# 03_MCU_STM32.net
KiCad netlist of a schematic drawn in Altium Designer
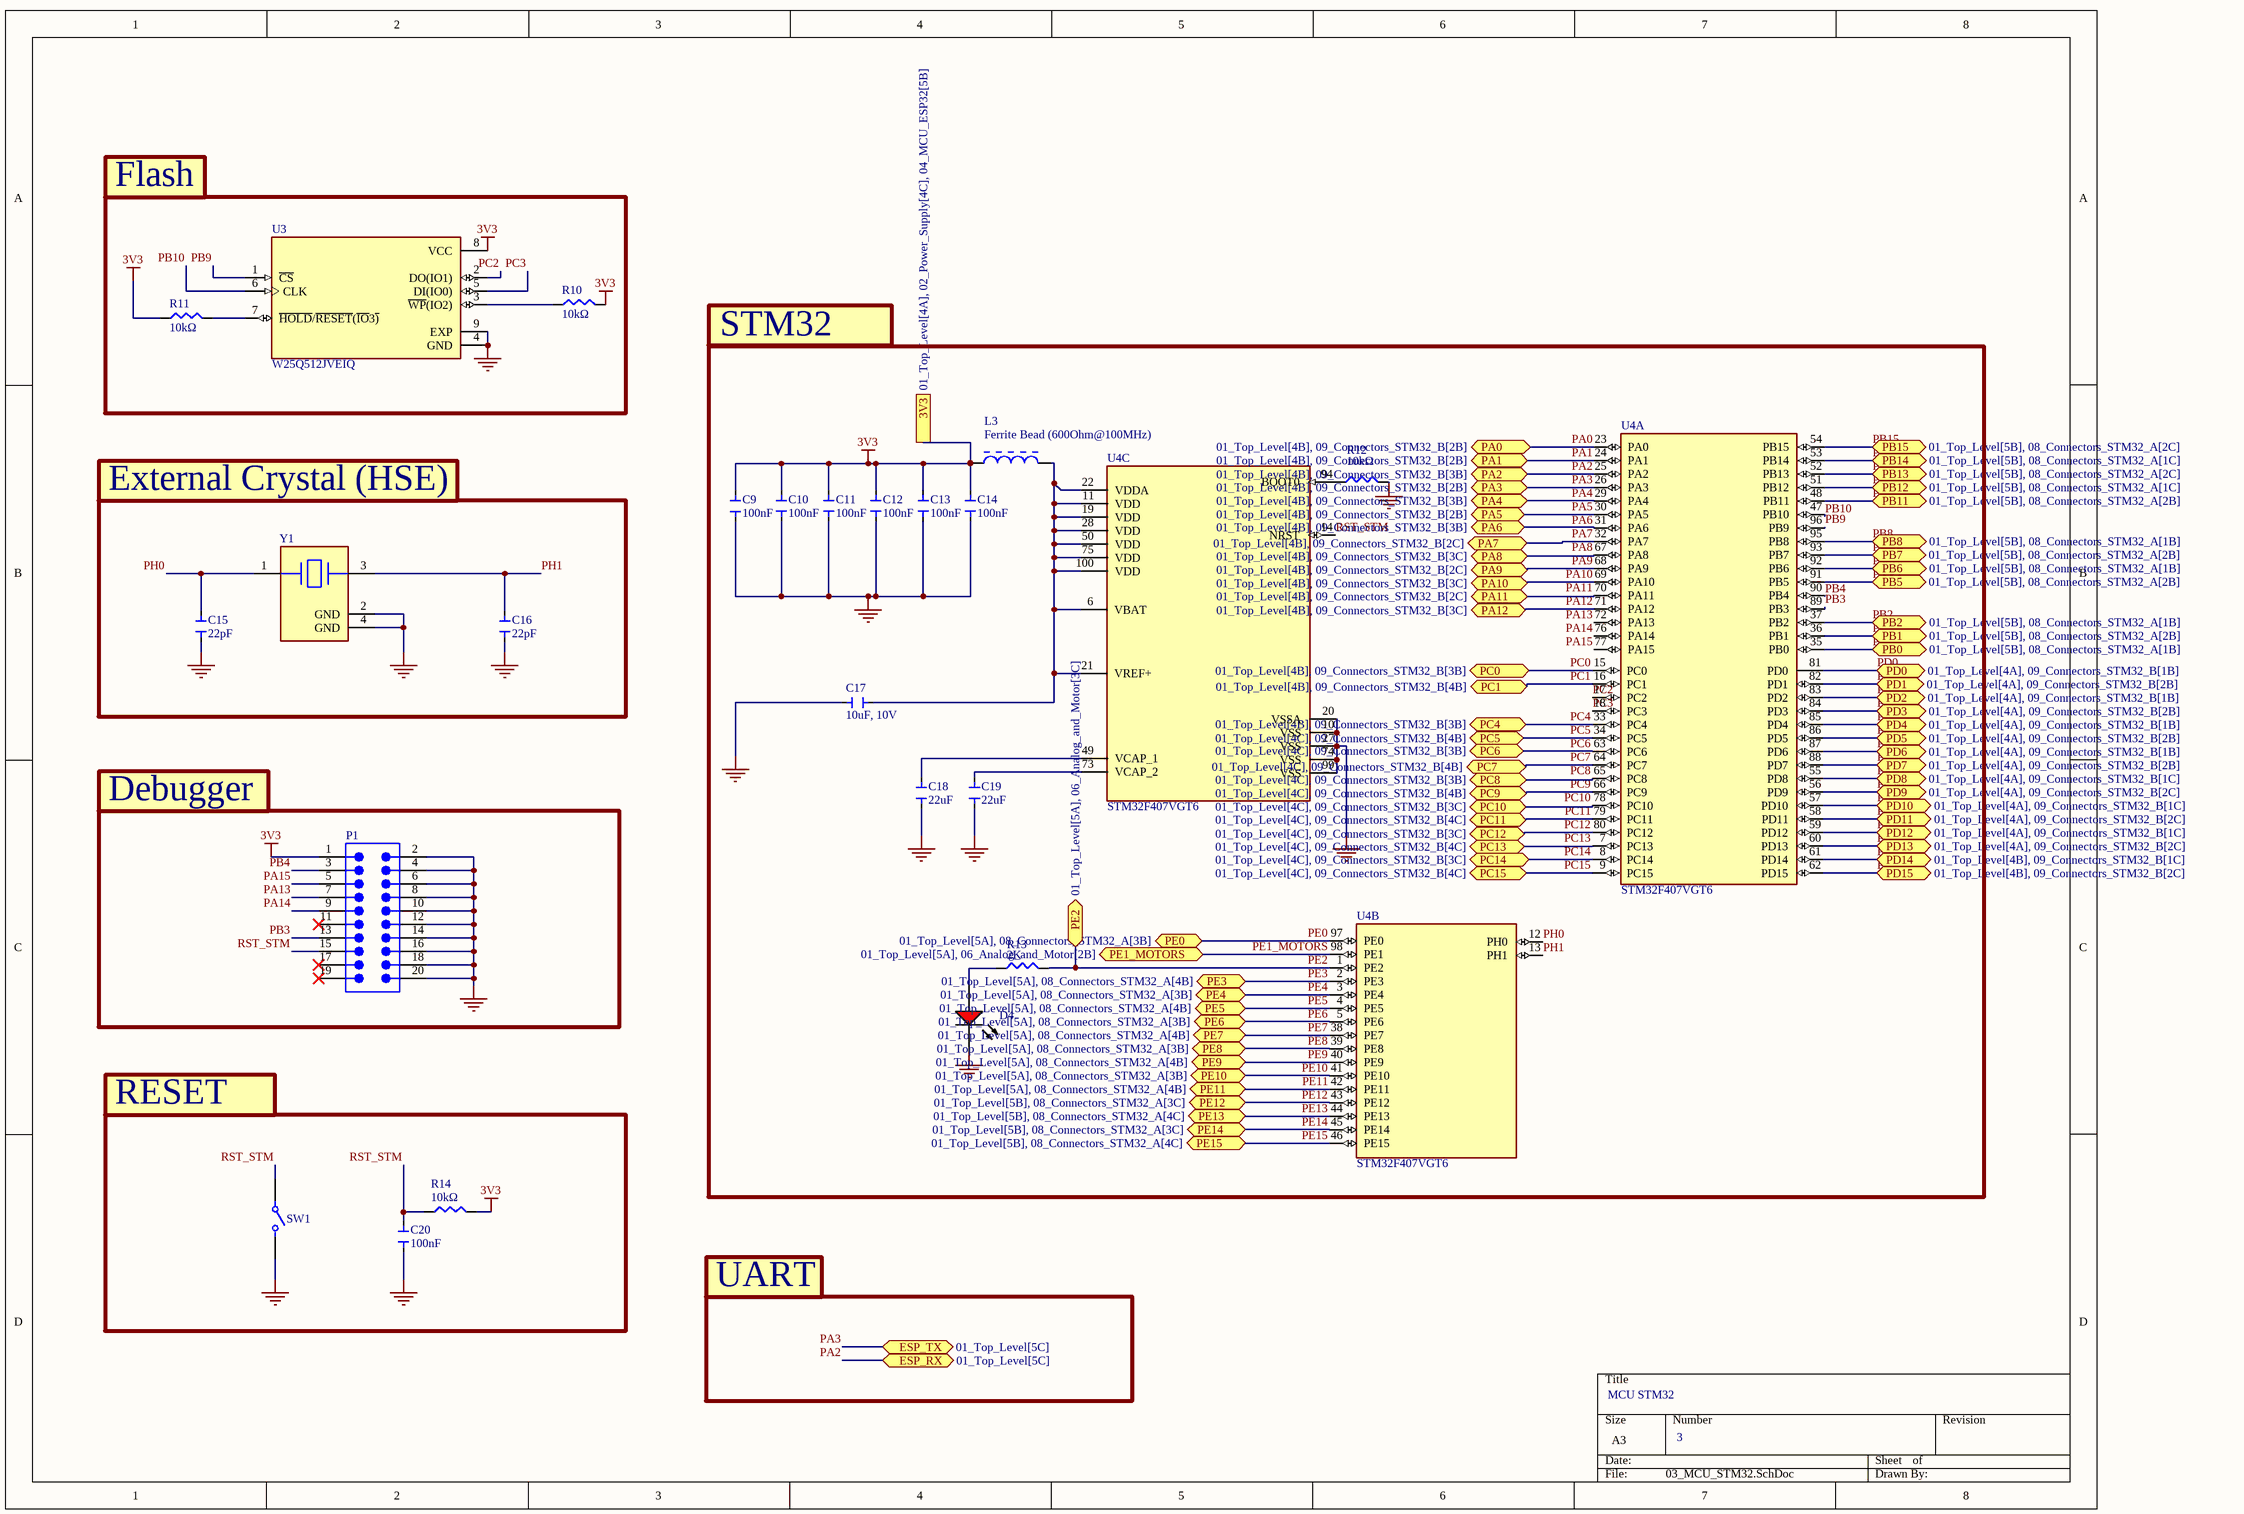
[diagram p0: 03_MCU_STM32.SchDoc]

(export (version "E")
  (design (tool "Eeschema 10.0.6"))
  (components
    (comp (ref "C9")
      (value "100nF")
      (footprint "CAP_100nF")
      (description "CAP 100nF 50V X7R ±10% 0603 Ceramic Capacitors RoHS")
      (fields
        (field (name "MANUFACTURER") "YAGEO")
        (field (name "MANUFACTURER PART NUMBER") "CC0603KRX7R9BB104")
      )
      (libsource (lib "Components_Schlib") (part "CAP_100nF"))
    )
    (comp (ref "C10")
      (value "100nF")
      (footprint "CAP_100nF")
      (description "CAP 100nF 50V X7R ±10% 0603 Ceramic Capacitors RoHS")
      (fields
        (field (name "MANUFACTURER") "YAGEO")
        (field (name "MANUFACTURER PART NUMBER") "CC0603KRX7R9BB104")
      )
      (libsource (lib "Components_Schlib") (part "CAP_100nF"))
    )
    (comp (ref "C11")
      (value "100nF")
      (footprint "CAP_100nF")
      (description "CAP 100nF 50V X7R ±10% 0603 Ceramic Capacitors RoHS")
      (fields
        (field (name "MANUFACTURER") "YAGEO")
        (field (name "MANUFACTURER PART NUMBER") "CC0603KRX7R9BB104")
      )
      (libsource (lib "Components_Schlib") (part "CAP_100nF"))
    )
    (comp (ref "C12")
      (value "100nF")
      (footprint "CAP_100nF")
      (description "CAP 100nF 50V X7R ±10% 0603 Ceramic Capacitors RoHS")
      (fields
        (field (name "MANUFACTURER") "YAGEO")
        (field (name "MANUFACTURER PART NUMBER") "CC0603KRX7R9BB104")
      )
      (libsource (lib "Components_Schlib") (part "CAP_100nF"))
    )
    (comp (ref "C13")
      (value "100nF")
      (footprint "CAP_100nF")
      (description "CAP 100nF 50V X7R ±10% 0603 Ceramic Capacitors RoHS")
      (fields
        (field (name "MANUFACTURER") "YAGEO")
        (field (name "MANUFACTURER PART NUMBER") "CC0603KRX7R9BB104")
      )
      (libsource (lib "Components_Schlib") (part "CAP_100nF"))
    )
    (comp (ref "C14")
      (value "100nF")
      (footprint "CAP_100nF")
      (description "CAP 100nF 50V X7R ±10% 0603 Ceramic Capacitors RoHS")
      (fields
        (field (name "MANUFACTURER") "YAGEO")
        (field (name "MANUFACTURER PART NUMBER") "CC0603KRX7R9BB104")
      )
      (libsource (lib "Components_Schlib") (part "CAP_100nF"))
    )
    (comp (ref "C15")
      (value "22pF")
      (footprint "CAP_22uF")
      (description "CAP 22uF 25V X5R ±20% 0805 Ceramic Capacitors RoHS")
      (fields
        (field (name "MANUFACTURER") "Samsung Electro-Mechanics")
        (field (name "MANUFACTURER PART NUMBER") "CL21A226MAYNNNE")
      )
      (libsource (lib "Components_Schlib") (part "CAP_22uF"))
    )
    (comp (ref "C16")
      (value "22pF")
      (footprint "CAP_22uF")
      (description "CAP 22uF 25V X5R ±20% 0805 Ceramic Capacitors RoHS")
      (fields
        (field (name "MANUFACTURER") "Samsung Electro-Mechanics")
        (field (name "MANUFACTURER PART NUMBER") "CL21A226MAYNNNE")
      )
      (libsource (lib "Components_Schlib") (part "CAP_22uF"))
    )
    (comp (ref "C17")
      (value "10uF, 10V")
      (footprint "CAP_10uF")
      (description "CAP CER 10UF 10V X5R 0402")
      (fields
        (field (name "MANUFACTURER") "Samsung Electro-Mechanics")
        (field (name "MANUFACTURER PART NUMBER") "C307415")
      )
      (libsource (lib "Components_Schlib") (part "CAP_0402_10UF"))
    )
    (comp (ref "C18")
      (value "22uF")
      (footprint "CAP_22uF")
      (description "CAP 22uF 25V X5R ±20% 0805 Ceramic Capacitors RoHS")
      (fields
        (field (name "MANUFACTURER") "Samsung Electro-Mechanics")
        (field (name "MANUFACTURER PART NUMBER") "CL21A226MAYNNNE")
      )
      (libsource (lib "Components_Schlib") (part "CAP_22uF"))
    )
    (comp (ref "C19")
      (value "22uF")
      (footprint "CAP_22uF")
      (description "CAP 22uF 25V X5R ±20% 0805 Ceramic Capacitors RoHS")
      (fields
        (field (name "MANUFACTURER") "Samsung Electro-Mechanics")
        (field (name "MANUFACTURER PART NUMBER") "CL21A226MAYNNNE")
      )
      (libsource (lib "Components_Schlib") (part "CAP_22uF"))
    )
    (comp (ref "C20")
      (value "100nF")
      (footprint "CAP_100nF")
      (description "CAP 100nF 50V X7R ±10% 0603 Ceramic Capacitors RoHS")
      (fields
        (field (name "MANUFACTURER") "YAGEO")
        (field (name "MANUFACTURER PART NUMBER") "CC0603KRX7R9BB104")
      )
      (libsource (lib "Components_Schlib") (part "CAP_100nF"))
    )
    (comp (ref "D4")
      (value "304090041")
      (footprint "LED-2P-2.28-3MM_A")
      (description "Red LED, 80 mW, 30 mA, -25 to 85 degC, 2-Pin THD")
      (fields (field (name "MANUFACTURER") "Shenzhen CGX"))
      (libsource (lib "Youssef Adel") (part "LED-RED-AK-2"))
    )
    (comp (ref "L3")
      (value "BLM18AG121SN1D")
      (footprint "MURA-BLM18-F-H1-CHIP-2_V")
      (fields (field (name "TOLERANCE") "25%") (field (name "MANUFACTURER") "Murata"))
      (libsource (lib "Youssef Adel") (part "IND-FB-2"))
    )
    (comp (ref "P1")
      (value "61002021121")
      (footprint "61002021121")
      (description "SMT Vertical Pin Header WR-PHD, Pitch 2.54 mm, Dual Row, 20 pins")
      (libsource (lib "Altium Content Vault") (part "Header_Male_2R_20P"))
    )
    (comp (ref "R10")
      (value "10kΩ")
      (footprint "RES_10K")
      (description "100mW Thin Film Resistor ±0.1% ±10ppm/℃ 10kΩ 0603 Chip Resistor - Surface Mount ROHS")
      (fields
        (field (name "MANUFACTURER") "Yageo Group")
        (field (name "MANUFACTURER PART NUMBER") "RT0603BRB07169KL")
      )
      (libsource (lib "Components_Schlib") (part "RES_0603_10K"))
    )
    (comp (ref "R11")
      (value "10kΩ")
      (footprint "RES_10K")
      (description "100mW Thin Film Resistor ±0.1% ±10ppm/℃ 10kΩ 0603 Chip Resistor - Surface Mount ROHS")
      (fields
        (field (name "MANUFACTURER") "Yageo Group")
        (field (name "MANUFACTURER PART NUMBER") "RT0603BRB07169KL")
      )
      (libsource (lib "Components_Schlib") (part "RES_0603_10K"))
    )
    (comp (ref "R12")
      (value "10kΩ")
      (footprint "RES_10K")
      (description "100mW Thin Film Resistor ±0.1% ±10ppm/℃ 10kΩ 0603 Chip Resistor - Surface Mount ROHS")
      (fields
        (field (name "MANUFACTURER") "Yageo Group")
        (field (name "MANUFACTURER PART NUMBER") "RT0603BRB07169KL")
      )
      (libsource (lib "Components_Schlib") (part "RES_0603_10K"))
    )
    (comp (ref "R13")
      (value "2K")
      (footprint "RES_2K")
      (description "100mW 2KΩ 75V Thick Film Resistor ±100ppm/℃ ±1% 0603 Chip Resistor - Surface Mount RoHS")
      (libsource (lib "Components_Schlib") (part "RSE_0603_2K"))
    )
    (comp (ref "R14")
      (value "10kΩ")
      (footprint "RES_10K")
      (description "100mW Thin Film Resistor ±0.1% ±10ppm/℃ 10kΩ 0603 Chip Resistor - Surface Mount ROHS")
      (fields
        (field (name "MANUFACTURER") "Yageo Group")
        (field (name "MANUFACTURER PART NUMBER") "RT0603BRB07169KL")
      )
      (libsource (lib "Components_Schlib") (part "RES_0603_10K"))
    )
    (comp (ref "SW1")
      (value "EVP-BD6C1A000")
      (footprint "FP-EVP-BD6C1A000-MFG")
      (description "EVP-BD6C1A000 Switch Tactile N.O. SPST Round Button J-Bend 0.05A 12VDC 3.5N SMD Automotive T/R")
      (libsource (lib "Altium Content Vault") (part "2b0b2b19372efd94fa7681498149756"))
    )
    (comp (ref "U3")
      (value "W25Q512JVEIQ")
      (footprint "SON127P600X800X80-9N")
      (description "FLASH - NOR Memory IC 512Mb (64M x 8) SPI - Quad I/O 133 MHz 8-WSON (8x6)")
      (fields (field (name "MF") "Winbond Electronics"))
      (libsource (lib "Components_Schlib") (part "W25Q512JVEIQ"))
    )
    (comp (ref "U4")
      (value "STM32F407VGT6")
      (footprint "QFP50P1600X1600X160-100N")
      (fields (field (name "MF") "STMicroelectronics"))
      (libsource (lib "Components_Schlib") (part "STM32F407VGT6"))
    )
    (comp (ref "Y1")
      (value "ABM11AIG-32.000MHZ-4-T3")
      (footprint "FP-ABM11AIG-MFG")
      (description "Crystal 32MHz ±30ppm 10pF SMD-4 2.5mm x 2mm Automotive")
      (libsource (lib "Altium Content Vault") (part "51b5329859b7ce12e0c2ce5858bdf70"))
    )
  )
  (nets
    (net (code "1") (name "/PA0") (class "Default")
      (node (ref "U4") (pin "23") (pinfunction "PA0_23") (pintype "bidirectional"))
    )
    (net (code "2") (name "/PA1") (class "Default")
      (node (ref "U4") (pin "24") (pinfunction "PA1_24") (pintype "bidirectional"))
    )
    (net (code "3") (name "/PA2") (class "Default")
      (node (ref "U4") (pin "25") (pinfunction "PA2_25") (pintype "bidirectional"))
    )
    (net (code "4") (name "/PA3") (class "Default")
      (node (ref "U4") (pin "26") (pinfunction "PA3_26") (pintype "bidirectional"))
    )
    (net (code "5") (name "/PA4") (class "Default")
      (node (ref "U4") (pin "29") (pinfunction "PA4_29") (pintype "bidirectional"))
    )
    (net (code "6") (name "/PA5") (class "Default")
      (node (ref "U4") (pin "30") (pinfunction "PA5_30") (pintype "bidirectional"))
    )
    (net (code "7") (name "/PA6") (class "Default")
      (node (ref "U4") (pin "31") (pinfunction "PA6_31") (pintype "bidirectional"))
    )
    (net (code "8") (name "/PA7") (class "Default")
      (node (ref "U4") (pin "32") (pinfunction "PA7_32") (pintype "bidirectional"))
    )
    (net (code "9") (name "/PA8") (class "Default")
      (node (ref "U4") (pin "67") (pinfunction "PA8_67") (pintype "bidirectional"))
    )
    (net (code "10") (name "/PA9") (class "Default")
      (node (ref "U4") (pin "68") (pinfunction "PA9_68") (pintype "bidirectional"))
    )
    (net (code "11") (name "/PA10") (class "Default")
      (node (ref "U4") (pin "69") (pinfunction "PA10_69") (pintype "bidirectional"))
    )
    (net (code "12") (name "/PA11") (class "Default")
      (node (ref "U4") (pin "70") (pinfunction "PA11_70") (pintype "bidirectional"))
    )
    (net (code "13") (name "/PA12") (class "Default")
      (node (ref "U4") (pin "71") (pinfunction "PA12_71") (pintype "bidirectional"))
    )
    (net (code "14") (name "/PA13") (class "Default")
      (node (ref "P1") (pin "7") (pinfunction "7_7") (pintype "passive"))
      (node (ref "U4") (pin "72") (pinfunction "PA13_72") (pintype "bidirectional"))
    )
    (net (code "15") (name "/PA14") (class "Default")
      (node (ref "P1") (pin "9") (pinfunction "9_9") (pintype "passive"))
      (node (ref "U4") (pin "76") (pinfunction "PA14_76") (pintype "bidirectional"))
    )
    (net (code "16") (name "/PA15") (class "Default")
      (node (ref "P1") (pin "5") (pinfunction "5_5") (pintype "passive"))
      (node (ref "U4") (pin "77") (pinfunction "PA15_77") (pintype "bidirectional"))
    )
    (net (code "17") (name "/PB0") (class "Default")
      (node (ref "U4") (pin "35") (pinfunction "PB0_35") (pintype "bidirectional"))
    )
    (net (code "18") (name "/PB1") (class "Default")
      (node (ref "U4") (pin "36") (pinfunction "PB1_36") (pintype "bidirectional"))
    )
    (net (code "19") (name "/PB2") (class "Default")
      (node (ref "U4") (pin "37") (pinfunction "PB2_37") (pintype "bidirectional"))
    )
    (net (code "20") (name "/PB3") (class "Default")
      (node (ref "P1") (pin "13") (pinfunction "13_13") (pintype "passive"))
      (node (ref "U4") (pin "89") (pinfunction "PB3_89") (pintype "bidirectional"))
    )
    (net (code "21") (name "/PB4") (class "Default")
      (node (ref "P1") (pin "3") (pinfunction "3_3") (pintype "passive"))
      (node (ref "U4") (pin "90") (pinfunction "PB4_90") (pintype "bidirectional"))
    )
    (net (code "22") (name "/PB5") (class "Default")
      (node (ref "U4") (pin "91") (pinfunction "PB5_91") (pintype "bidirectional"))
    )
    (net (code "23") (name "/PB6") (class "Default")
      (node (ref "U4") (pin "92") (pinfunction "PB6_92") (pintype "bidirectional"))
    )
    (net (code "24") (name "/PB7") (class "Default")
      (node (ref "U4") (pin "93") (pinfunction "PB7_93") (pintype "bidirectional"))
    )
    (net (code "25") (name "/PB8") (class "Default")
      (node (ref "U4") (pin "95") (pinfunction "PB8_95") (pintype "bidirectional"))
    )
    (net (code "26") (name "/PB9") (class "Default")
      (node (ref "U3") (pin "1") (pinfunction "~{CS}_1") (pintype "input"))
      (node (ref "U4") (pin "96") (pinfunction "PB9_96") (pintype "bidirectional"))
    )
    (net (code "27") (name "/PB10") (class "Default")
      (node (ref "U3") (pin "6") (pinfunction "CLK_6") (pintype "input"))
      (node (ref "U4") (pin "47") (pinfunction "PB10_47") (pintype "bidirectional"))
    )
    (net (code "28") (name "/PB11") (class "Default")
      (node (ref "U4") (pin "48") (pinfunction "PB11_48") (pintype "bidirectional"))
    )
    (net (code "29") (name "/PB12") (class "Default")
      (node (ref "U4") (pin "51") (pinfunction "PB12_51") (pintype "bidirectional"))
    )
    (net (code "30") (name "/PB13") (class "Default")
      (node (ref "U4") (pin "52") (pinfunction "PB13_52") (pintype "bidirectional"))
    )
    (net (code "31") (name "/PB14") (class "Default")
      (node (ref "U4") (pin "53") (pinfunction "PB14_53") (pintype "bidirectional"))
    )
    (net (code "32") (name "/PB15") (class "Default")
      (node (ref "U4") (pin "54") (pinfunction "PB15_54") (pintype "bidirectional"))
    )
    (net (code "33") (name "/PC0") (class "Default")
      (node (ref "U4") (pin "15") (pinfunction "PC0_15") (pintype "bidirectional"))
    )
    (net (code "34") (name "/PC1") (class "Default")
      (node (ref "U4") (pin "16") (pinfunction "PC1_16") (pintype "bidirectional"))
    )
    (net (code "35") (name "/PC2") (class "Default")
      (node (ref "U3") (pin "2") (pinfunction "DO(IO1)_2") (pintype "bidirectional"))
      (node (ref "U4") (pin "17") (pinfunction "PC2_17") (pintype "bidirectional"))
    )
    (net (code "36") (name "/PC3") (class "Default")
      (node (ref "U3") (pin "5") (pinfunction "DI(IO0)_5") (pintype "bidirectional"))
      (node (ref "U4") (pin "18") (pinfunction "PC3_18") (pintype "bidirectional"))
    )
    (net (code "37") (name "/PC4") (class "Default")
      (node (ref "U4") (pin "33") (pinfunction "PC4_33") (pintype "bidirectional"))
    )
    (net (code "38") (name "/PC5") (class "Default")
      (node (ref "U4") (pin "34") (pinfunction "PC5_34") (pintype "bidirectional"))
    )
    (net (code "39") (name "/PC6") (class "Default")
      (node (ref "U4") (pin "63") (pinfunction "PC6_63") (pintype "bidirectional"))
    )
    (net (code "40") (name "/PC7") (class "Default")
      (node (ref "U4") (pin "64") (pinfunction "PC7_64") (pintype "bidirectional"))
    )
    (net (code "41") (name "/PC8") (class "Default")
      (node (ref "U4") (pin "65") (pinfunction "PC8_65") (pintype "bidirectional"))
    )
    (net (code "42") (name "/PC9") (class "Default")
      (node (ref "U4") (pin "66") (pinfunction "PC9_66") (pintype "bidirectional"))
    )
    (net (code "43") (name "/PC10") (class "Default")
      (node (ref "U4") (pin "78") (pinfunction "PC10_78") (pintype "bidirectional"))
    )
    (net (code "44") (name "/PC11") (class "Default")
      (node (ref "U4") (pin "79") (pinfunction "PC11_79") (pintype "bidirectional"))
    )
    (net (code "45") (name "/PC12") (class "Default")
      (node (ref "U4") (pin "80") (pinfunction "PC12_80") (pintype "bidirectional"))
    )
    (net (code "46") (name "/PC13") (class "Default")
      (node (ref "U4") (pin "7") (pinfunction "PC13_7") (pintype "bidirectional"))
    )
    (net (code "47") (name "/PC14") (class "Default")
      (node (ref "U4") (pin "8") (pinfunction "PC14_8") (pintype "bidirectional"))
    )
    (net (code "48") (name "/PC15") (class "Default")
      (node (ref "U4") (pin "9") (pinfunction "PC15_9") (pintype "bidirectional"))
    )
    (net (code "49") (name "/PD0") (class "Default")
      (node (ref "U4") (pin "81") (pinfunction "PD0_81") (pintype "bidirectional"))
    )
    (net (code "50") (name "/PD1") (class "Default")
      (node (ref "U4") (pin "82") (pinfunction "PD1_82") (pintype "bidirectional"))
    )
    (net (code "51") (name "/PD2") (class "Default")
      (node (ref "U4") (pin "83") (pinfunction "PD2_83") (pintype "bidirectional"))
    )
    (net (code "52") (name "/PD3") (class "Default")
      (node (ref "U4") (pin "84") (pinfunction "PD3_84") (pintype "bidirectional"))
    )
    (net (code "53") (name "/PD4") (class "Default")
      (node (ref "U4") (pin "85") (pinfunction "PD4_85") (pintype "bidirectional"))
    )
    (net (code "54") (name "/PD5") (class "Default")
      (node (ref "U4") (pin "86") (pinfunction "PD5_86") (pintype "bidirectional"))
    )
    (net (code "55") (name "/PD6") (class "Default")
      (node (ref "U4") (pin "87") (pinfunction "PD6_87") (pintype "bidirectional"))
    )
    (net (code "56") (name "/PD7") (class "Default")
      (node (ref "U4") (pin "88") (pinfunction "PD7_88") (pintype "bidirectional"))
    )
    (net (code "57") (name "/PD8") (class "Default")
      (node (ref "U4") (pin "55") (pinfunction "PD8_55") (pintype "bidirectional"))
    )
    (net (code "58") (name "/PD9") (class "Default")
      (node (ref "U4") (pin "56") (pinfunction "PD9_56") (pintype "bidirectional"))
    )
    (net (code "59") (name "/PD10") (class "Default")
      (node (ref "U4") (pin "57") (pinfunction "PD10_57") (pintype "bidirectional"))
    )
    (net (code "60") (name "/PD11") (class "Default")
      (node (ref "U4") (pin "58") (pinfunction "PD11_58") (pintype "bidirectional"))
    )
    (net (code "61") (name "/PD12") (class "Default")
      (node (ref "U4") (pin "59") (pinfunction "PD12_59") (pintype "bidirectional"))
    )
    (net (code "62") (name "/PD13") (class "Default")
      (node (ref "U4") (pin "60") (pinfunction "PD13_60") (pintype "bidirectional"))
    )
    (net (code "63") (name "/PD14") (class "Default")
      (node (ref "U4") (pin "61") (pinfunction "PD14_61") (pintype "bidirectional"))
    )
    (net (code "64") (name "/PD15") (class "Default")
      (node (ref "U4") (pin "62") (pinfunction "PD15_62") (pintype "bidirectional"))
    )
    (net (code "65") (name "/PE0") (class "Default")
      (node (ref "U4") (pin "97") (pinfunction "PE0_97") (pintype "bidirectional"))
    )
    (net (code "66") (name "/PE1_MOTORS") (class "Default")
      (node (ref "U4") (pin "98") (pinfunction "PE1_98") (pintype "bidirectional"))
    )
    (net (code "67") (name "/PE2") (class "Default")
      (node (ref "R13") (pin "2") (pinfunction "2_2") (pintype "passive"))
      (node (ref "U4") (pin "1") (pinfunction "PE2_1") (pintype "bidirectional"))
    )
    (net (code "68") (name "/PE3") (class "Default")
      (node (ref "U4") (pin "2") (pinfunction "PE3_2") (pintype "bidirectional"))
    )
    (net (code "69") (name "/PE4") (class "Default")
      (node (ref "U4") (pin "3") (pinfunction "PE4_3") (pintype "bidirectional"))
    )
    (net (code "70") (name "/PE5") (class "Default")
      (node (ref "U4") (pin "4") (pinfunction "PE5_4") (pintype "bidirectional"))
    )
    (net (code "71") (name "/PE6") (class "Default")
      (node (ref "U4") (pin "5") (pinfunction "PE6_5") (pintype "bidirectional"))
    )
    (net (code "72") (name "/PE7") (class "Default")
      (node (ref "U4") (pin "38") (pinfunction "PE7_38") (pintype "bidirectional"))
    )
    (net (code "73") (name "/PE8") (class "Default")
      (node (ref "U4") (pin "39") (pinfunction "PE8_39") (pintype "bidirectional"))
    )
    (net (code "74") (name "/PE9") (class "Default")
      (node (ref "U4") (pin "40") (pinfunction "PE9_40") (pintype "bidirectional"))
    )
    (net (code "75") (name "/PE10") (class "Default")
      (node (ref "U4") (pin "41") (pinfunction "PE10_41") (pintype "bidirectional"))
    )
    (net (code "76") (name "/PE11") (class "Default")
      (node (ref "U4") (pin "42") (pinfunction "PE11_42") (pintype "bidirectional"))
    )
    (net (code "77") (name "/PE12") (class "Default")
      (node (ref "U4") (pin "43") (pinfunction "PE12_43") (pintype "bidirectional"))
    )
    (net (code "78") (name "/PE13") (class "Default")
      (node (ref "U4") (pin "44") (pinfunction "PE13_44") (pintype "bidirectional"))
    )
    (net (code "79") (name "/PE14") (class "Default")
      (node (ref "U4") (pin "45") (pinfunction "PE14_45") (pintype "bidirectional"))
    )
    (net (code "80") (name "/PE15") (class "Default")
      (node (ref "U4") (pin "46") (pinfunction "PE15_46") (pintype "bidirectional"))
    )
    (net (code "81") (name "/PH0") (class "Default")
      (node (ref "C15") (pin "2") (pinfunction "2_2") (pintype "passive"))
      (node (ref "U4") (pin "12") (pinfunction "PH0_12") (pintype "bidirectional"))
      (node (ref "Y1") (pin "1") (pinfunction "1_Crystal_1") (pintype "passive"))
    )
    (net (code "82") (name "/PH1") (class "Default")
      (node (ref "C16") (pin "2") (pinfunction "2_2") (pintype "passive"))
      (node (ref "U4") (pin "13") (pinfunction "PH1_13") (pintype "bidirectional"))
      (node (ref "Y1") (pin "3") (pinfunction "2_Crystal_3") (pintype "passive"))
    )
    (net (code "83") (name "/RST_STM") (class "Default")
      (node (ref "C20") (pin "2") (pinfunction "2_2") (pintype "passive"))
      (node (ref "P1") (pin "15") (pinfunction "15_15") (pintype "passive"))
      (node (ref "R14") (pin "1") (pinfunction "1_1") (pintype "passive"))
      (node (ref "SW1") (pin "A") (pinfunction "A_A") (pintype "passive"))
      (node (ref "U4") (pin "14") (pinfunction "NRST_14") (pintype "bidirectional"))
    )
    (net (code "84") (name "3V3") (class "Default")
      (node (ref "C10") (pin "2") (pinfunction "2_2") (pintype "passive"))
      (node (ref "C11") (pin "2") (pinfunction "2_2") (pintype "passive"))
      (node (ref "C12") (pin "2") (pinfunction "2_2") (pintype "passive"))
      (node (ref "C13") (pin "2") (pinfunction "2_2") (pintype "passive"))
      (node (ref "C14") (pin "2") (pinfunction "2_2") (pintype "passive"))
      (node (ref "C9") (pin "2") (pinfunction "2_2") (pintype "passive"))
      (node (ref "L3") (pin "1") (pinfunction "1_1") (pintype "passive"))
      (node (ref "P1") (pin "1") (pinfunction "1_1") (pintype "passive"))
      (node (ref "R10") (pin "2") (pinfunction "2_2") (pintype "passive"))
      (node (ref "R11") (pin "1") (pinfunction "1_1") (pintype "passive"))
      (node (ref "R14") (pin "2") (pinfunction "2_2") (pintype "passive"))
      (node (ref "U3") (pin "8") (pinfunction "VCC_8") (pintype "power_in"))
    )
    (net (code "85") (name "GND") (class "Default")
      (node (ref "C10") (pin "1") (pinfunction "1_1") (pintype "passive"))
      (node (ref "C11") (pin "1") (pinfunction "1_1") (pintype "passive"))
      (node (ref "C12") (pin "1") (pinfunction "1_1") (pintype "passive"))
      (node (ref "C13") (pin "1") (pinfunction "1_1") (pintype "passive"))
      (node (ref "C14") (pin "1") (pinfunction "1_1") (pintype "passive"))
      (node (ref "C15") (pin "1") (pinfunction "1_1") (pintype "passive"))
      (node (ref "C16") (pin "1") (pinfunction "1_1") (pintype "passive"))
      (node (ref "C17") (pin "1") (pinfunction "1_1") (pintype "passive"))
      (node (ref "C18") (pin "2") (pinfunction "2_2") (pintype "passive"))
      (node (ref "C19") (pin "2") (pinfunction "2_2") (pintype "passive"))
      (node (ref "C20") (pin "1") (pinfunction "1_1") (pintype "passive"))
      (node (ref "C9") (pin "1") (pinfunction "1_1") (pintype "passive"))
      (node (ref "D4") (pin "2") (pinfunction "K_2") (pintype "passive"))
      (node (ref "P1") (pin "10") (pinfunction "10_10") (pintype "passive"))
      (node (ref "P1") (pin "12") (pinfunction "12_12") (pintype "passive"))
      (node (ref "P1") (pin "14") (pinfunction "14_14") (pintype "passive"))
      (node (ref "P1") (pin "16") (pinfunction "16_16") (pintype "passive"))
      (node (ref "P1") (pin "18") (pinfunction "18_18") (pintype "passive"))
      (node (ref "P1") (pin "2") (pinfunction "2_2") (pintype "passive"))
      (node (ref "P1") (pin "20") (pinfunction "20_20") (pintype "passive"))
      (node (ref "P1") (pin "4") (pinfunction "4_4") (pintype "passive"))
      (node (ref "P1") (pin "6") (pinfunction "6_6") (pintype "passive"))
      (node (ref "P1") (pin "8") (pinfunction "8_8") (pintype "passive"))
      (node (ref "R12") (pin "2") (pinfunction "2_2") (pintype "passive"))
      (node (ref "SW1") (pin "B") (pinfunction "B_B") (pintype "passive"))
      (node (ref "U3") (pin "4") (pinfunction "GND_4") (pintype "power_in"))
      (node (ref "U3") (pin "9") (pinfunction "EXP_9") (pintype "passive"))
      (node (ref "U4") (pin "10") (pinfunction "VSS_10") (pintype "power_in"))
      (node (ref "U4") (pin "20") (pinfunction "VSSA_20") (pintype "power_in"))
      (node (ref "U4") (pin "27") (pinfunction "VSS_27") (pintype "power_in"))
      (node (ref "U4") (pin "74") (pinfunction "VSS_74") (pintype "power_in"))
      (node (ref "U4") (pin "99") (pinfunction "VSS_99") (pintype "power_in"))
      (node (ref "Y1") (pin "2") (pinfunction "GND_2") (pintype "power_in"))
      (node (ref "Y1") (pin "4") (pinfunction "GND_4") (pintype "power_in"))
    )
    (net (code "86") (name "Net-(D4-A)") (class "Default")
      (node (ref "D4") (pin "1") (pinfunction "A_1") (pintype "passive"))
      (node (ref "R13") (pin "1") (pinfunction "1_1") (pintype "passive"))
    )
    (net (code "87") (name "Net-(U3-~{HOLD}{slash}~{RESET}(~{IO}3~{)})") (class "Default")
      (node (ref "R11") (pin "2") (pinfunction "2_2") (pintype "passive"))
      (node (ref "U3") (pin "7") (pinfunction "~{HOLD}/~{RESET}(~{IO}3~{)}_7") (pintype "bidirectional"))
    )
    (net (code "88") (name "Net-(U3-~{WP}(IO2))") (class "Default")
      (node (ref "R10") (pin "1") (pinfunction "1_1") (pintype "passive"))
      (node (ref "U3") (pin "3") (pinfunction "~{WP}(IO2)_3") (pintype "bidirectional"))
    )
    (net (code "89") (name "Net-(U4C-BOOT0)") (class "Default")
      (node (ref "R12") (pin "1") (pinfunction "1_1") (pintype "passive"))
      (node (ref "U4") (pin "94") (pinfunction "BOOT0_94") (pintype "input"))
    )
    (net (code "90") (name "Net-(U4C-VBAT)") (class "Default")
      (node (ref "C17") (pin "2") (pinfunction "2_2") (pintype "passive"))
      (node (ref "L3") (pin "2") (pinfunction "2_2") (pintype "passive"))
      (node (ref "U4") (pin "100") (pinfunction "VDD_100") (pintype "power_in"))
      (node (ref "U4") (pin "11") (pinfunction "VDD_11") (pintype "power_in"))
      (node (ref "U4") (pin "19") (pinfunction "VDD_19") (pintype "power_in"))
      (node (ref "U4") (pin "21") (pinfunction "VREF+_21") (pintype "power_in"))
      (node (ref "U4") (pin "22") (pinfunction "VDDA_22") (pintype "power_in"))
      (node (ref "U4") (pin "28") (pinfunction "VDD_28") (pintype "power_in"))
      (node (ref "U4") (pin "50") (pinfunction "VDD_50") (pintype "power_in"))
      (node (ref "U4") (pin "6") (pinfunction "VBAT_6") (pintype "power_in"))
      (node (ref "U4") (pin "75") (pinfunction "VDD_75") (pintype "power_in"))
    )
    (net (code "91") (name "Net-(U4C-VCAP_1)") (class "Default")
      (node (ref "C18") (pin "1") (pinfunction "1_1") (pintype "passive"))
      (node (ref "U4") (pin "49") (pinfunction "VCAP_1_49") (pintype "passive"))
    )
    (net (code "92") (name "Net-(U4C-VCAP_2)") (class "Default")
      (node (ref "C19") (pin "1") (pinfunction "1_1") (pintype "passive"))
      (node (ref "U4") (pin "73") (pinfunction "VCAP_2_73") (pintype "passive"))
    )
    (net (code "93") (name "unconnected-(P1-Pad11)") (class "Default")
      (node (ref "P1") (pin "11") (pinfunction "11_11") (pintype "passive+no_connect"))
    )
    (net (code "94") (name "unconnected-(P1-Pad17)") (class "Default")
      (node (ref "P1") (pin "17") (pinfunction "17_17") (pintype "passive+no_connect"))
    )
    (net (code "95") (name "unconnected-(P1-Pad19)") (class "Default")
      (node (ref "P1") (pin "19") (pinfunction "19_19") (pintype "passive+no_connect"))
    )
  )
)
